# tick-wifi-mini-mk-1_3.net
KiCad netlist of a schematic drawn in EAGLE
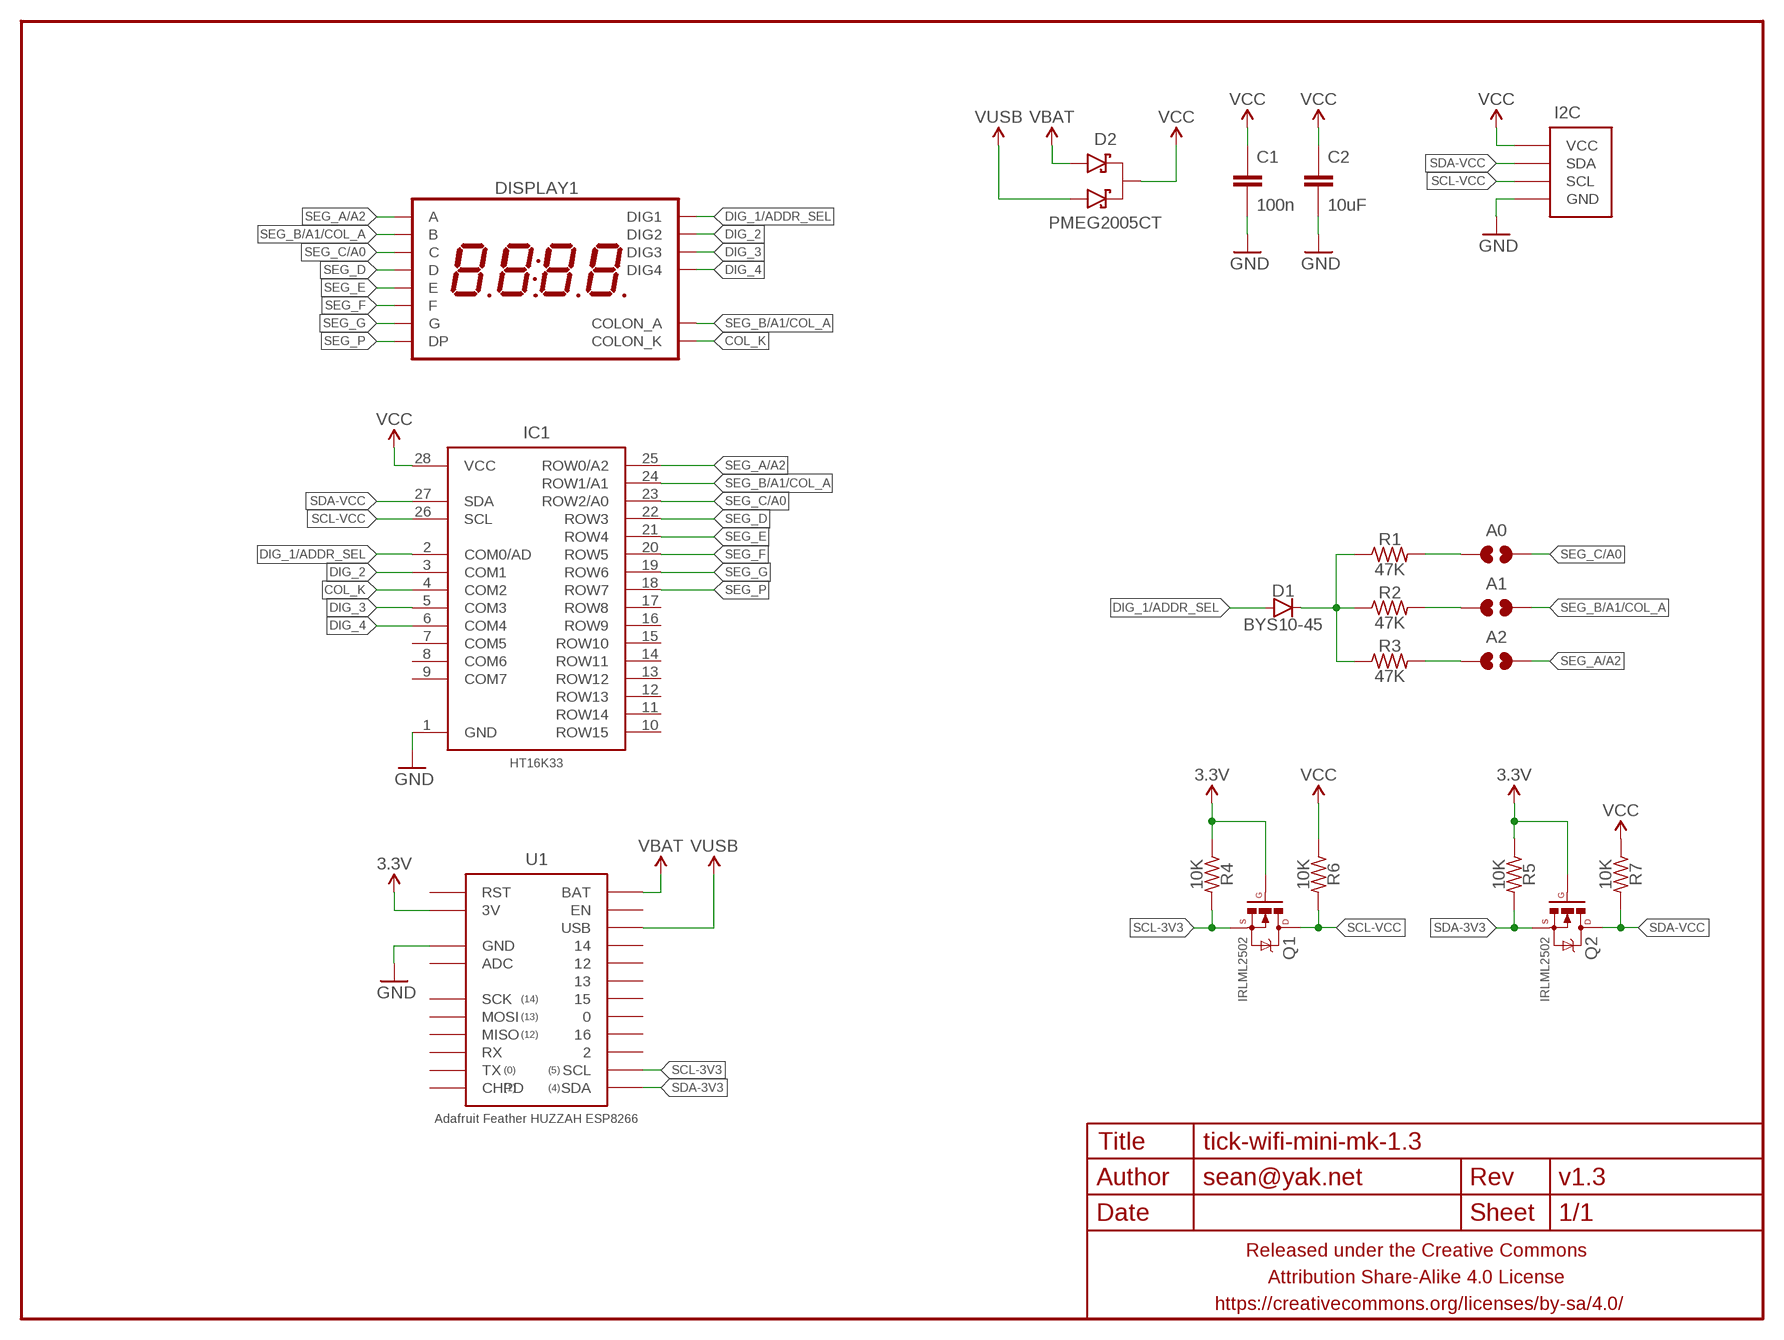
[diagram p0: schematic, sheet 1]

(export (version "E")
  (design (tool "Eeschema 10.0.6"))
  (components
    (comp (ref "A0")
      (value "JUMPER-PAD-2-NOYES_SILK")
      (footprint "eagle-import:PAD-JUMPER-2-NO_YES_SILK")
      (libsource (lib "eagle-import") (part "JUMPER-PAD-2-NOYES_SILK"))
    )
    (comp (ref "A1")
      (value "JUMPER-PAD-2-NOYES_SILK")
      (footprint "eagle-import:PAD-JUMPER-2-NO_YES_SILK")
      (libsource (lib "eagle-import") (part "JUMPER-PAD-2-NOYES_SILK"))
    )
    (comp (ref "A2")
      (value "JUMPER-PAD-2-NOYES_SILK")
      (footprint "eagle-import:PAD-JUMPER-2-NO_YES_SILK")
      (libsource (lib "eagle-import") (part "JUMPER-PAD-2-NOYES_SILK"))
    )
    (comp (ref "C1")
      (value "100n")
      (footprint "eagle-import:C0603-TIGHTER")
      (libsource (lib "eagle-import") (part "CAPACITOR-CERAMICC0603-TIGHTER"))
    )
    (comp (ref "C2")
      (value "10uF")
      (footprint "eagle-import:C0805-TIGHTER")
      (libsource (lib "eagle-import") (part "CAPACITOR-CERAMICC0805-TIGHTER"))
    )
    (comp (ref "D1")
      (value "BYS10-45")
      (footprint "eagle-import:SOD323")
      (libsource (lib "eagle-import") (part "DIODESOD"))
    )
    (comp (ref "D2")
      (value "PMEG2005CT")
      (footprint "eagle-import:SOT23")
      (libsource (lib "eagle-import") (part "DIODE-SCHOTTKY-DUALPMEG2005CT"))
    )
    (comp (ref "DISPLAY1")
      (value "7SEG_4DIGIT_COLON14.2MM-CC")
      (footprint "eagle-import:7SEG_4DIG_0.56IN_14MM_ADAFRUIT")
      (libsource (lib "eagle-import") (part "7SEG_4DIGIT_COLON14.2MM-CC"))
    )
    (comp (ref "FRAME1")
      (value "FRAME-LETTERNO_PACKAGE")
      (footprint "eagle-import:DUMMY")
      (fields (field (name "DESIGNER") "sean@yak.net") (field (name "VERSION") "v1.3"))
      (libsource (lib "eagle-import") (part "FRAME-LETTERNO_PACKAGE"))
    )
    (comp (ref "I2C")
      (value "M04-I2CPTH-2MM-CENTERED")
      (footprint "eagle-import:1X04-2MM-CENTERED-I2C")
      (libsource (lib "eagle-import") (part "M04-I2CPTH-2MM-CENTERED"))
    )
    (comp (ref "IC1")
      (value "HT16K33")
      (footprint "eagle-import:SOIC28W")
      (libsource (lib "eagle-import") (part "HT16K33-28SOIC28W"))
    )
    (comp (ref "Q1")
      (value "IRLML2502")
      (footprint "eagle-import:SOT23")
      (libsource (lib "eagle-import") (part "MOSFET-NCHANNELIRLML2502"))
    )
    (comp (ref "Q2")
      (value "IRLML2502")
      (footprint "eagle-import:SOT23")
      (libsource (lib "eagle-import") (part "MOSFET-NCHANNELIRLML2502"))
    )
    (comp (ref "R1")
      (value "47K")
      (footprint "eagle-import:R0603-TIGHTER")
      (libsource (lib "eagle-import") (part "RESISTORR0603-TIGHTER"))
    )
    (comp (ref "R2")
      (value "47K")
      (footprint "eagle-import:R0603-TIGHTER")
      (libsource (lib "eagle-import") (part "RESISTORR0603-TIGHTER"))
    )
    (comp (ref "R3")
      (value "47K")
      (footprint "eagle-import:R0603-TIGHTER")
      (libsource (lib "eagle-import") (part "RESISTORR0603-TIGHTER"))
    )
    (comp (ref "R4")
      (value "10K")
      (footprint "eagle-import:R0603-TIGHTER")
      (libsource (lib "eagle-import") (part "RESISTORR0603-TIGHTER"))
    )
    (comp (ref "R5")
      (value "10K")
      (footprint "eagle-import:R0603-TIGHTER")
      (libsource (lib "eagle-import") (part "RESISTORR0603-TIGHTER"))
    )
    (comp (ref "R6")
      (value "10K")
      (footprint "eagle-import:R0603-TIGHTER")
      (libsource (lib "eagle-import") (part "RESISTORR0603-TIGHTER"))
    )
    (comp (ref "R7")
      (value "10K")
      (footprint "eagle-import:R0603-TIGHTER")
      (libsource (lib "eagle-import") (part "RESISTORR0603-TIGHTER"))
    )
    (comp (ref "U1")
      (value "Adafruit Feather HUZZAH ESP8266")
      (footprint "eagle-import:ADAFRUIT_FEATHER_HUZZAH_NOSILK")
      (libsource (lib "eagle-import") (part "ADAFRUIT_FEATHER_HUZZAH_ESP8266NOSILK"))
    )
  )
  (nets
    (net (code "1") (name "3.3V") (class "Default")
      (node (ref "Q1") (pin "1") (pinfunction "G_1") (pintype "passive"))
      (node (ref "Q2") (pin "1") (pinfunction "G_1") (pintype "passive"))
      (node (ref "R4") (pin "1") (pinfunction "1_1") (pintype "passive"))
      (node (ref "R5") (pin "1") (pinfunction "1_1") (pintype "passive"))
      (node (ref "U1") (pin "3V") (pinfunction "3V_3V") (pintype "bidirectional"))
    )
    (net (code "2") (name "COL_K") (class "Default")
      (node (ref "DISPLAY1") (pin "P$7") (pinfunction "COLON_K_P$7") (pintype "passive"))
      (node (ref "IC1") (pin "4") (pinfunction "COM2_4") (pintype "bidirectional"))
    )
    (net (code "3") (name "DIG_1{slash}ADDR_SEL") (class "Default")
      (node (ref "D1") (pin "A") (pinfunction "A_A") (pintype "passive"))
      (node (ref "DISPLAY1") (pin "P$14") (pinfunction "DIG1_P$14") (pintype "passive"))
      (node (ref "IC1") (pin "2") (pinfunction "COM0/AD_2") (pintype "bidirectional"))
    )
    (net (code "4") (name "DIG_2") (class "Default")
      (node (ref "DISPLAY1") (pin "P$11") (pinfunction "DIG2_P$11") (pintype "passive"))
      (node (ref "IC1") (pin "3") (pinfunction "COM1_3") (pintype "bidirectional"))
    )
    (net (code "5") (name "DIG_3") (class "Default")
      (node (ref "DISPLAY1") (pin "P$10") (pinfunction "DIG3_P$10") (pintype "passive"))
      (node (ref "IC1") (pin "5") (pinfunction "COM3_5") (pintype "bidirectional"))
    )
    (net (code "6") (name "DIG_4") (class "Default")
      (node (ref "DISPLAY1") (pin "P$6") (pinfunction "DIG4_P$6") (pintype "passive"))
      (node (ref "IC1") (pin "6") (pinfunction "COM4_6") (pintype "bidirectional"))
    )
    (net (code "7") (name "GND") (class "Default")
      (node (ref "C1") (pin "2") (pinfunction "2_2") (pintype "passive"))
      (node (ref "C2") (pin "2") (pinfunction "2_2") (pintype "passive"))
      (node (ref "I2C") (pin "1") (pinfunction "GND_1") (pintype "bidirectional"))
      (node (ref "IC1") (pin "1") (pinfunction "GND_1") (pintype "bidirectional"))
      (node (ref "U1") (pin "GND@0") (pinfunction "GND_GND@0") (pintype "bidirectional"))
    )
    (net (code "8") (name "Net-(A0-Pad1)") (class "Default")
      (node (ref "A0") (pin "1") (pinfunction "1_1") (pintype "passive"))
      (node (ref "R1") (pin "2") (pinfunction "2_2") (pintype "passive"))
    )
    (net (code "9") (name "Net-(A1-Pad1)") (class "Default")
      (node (ref "A1") (pin "1") (pinfunction "1_1") (pintype "passive"))
      (node (ref "R2") (pin "2") (pinfunction "2_2") (pintype "passive"))
    )
    (net (code "10") (name "Net-(A2-Pad1)") (class "Default")
      (node (ref "A2") (pin "1") (pinfunction "1_1") (pintype "passive"))
      (node (ref "R3") (pin "2") (pinfunction "2_2") (pintype "passive"))
    )
    (net (code "11") (name "Net-(D1-PadC)") (class "Default")
      (node (ref "D1") (pin "C") (pinfunction "C_C") (pintype "passive"))
      (node (ref "R1") (pin "1") (pinfunction "1_1") (pintype "passive"))
      (node (ref "R2") (pin "1") (pinfunction "1_1") (pintype "passive"))
      (node (ref "R3") (pin "1") (pinfunction "1_1") (pintype "passive"))
    )
    (net (code "12") (name "SCL-3V3") (class "Default")
      (node (ref "Q1") (pin "2") (pinfunction "S_2") (pintype "passive"))
      (node (ref "R4") (pin "2") (pinfunction "2_2") (pintype "passive"))
      (node (ref "U1") (pin "SCL") (pinfunction "SCL_SCL") (pintype "bidirectional"))
    )
    (net (code "13") (name "SCL-VCC") (class "Default")
      (node (ref "I2C") (pin "4") (pinfunction "SCL_4") (pintype "bidirectional"))
      (node (ref "IC1") (pin "26") (pinfunction "SCL_26") (pintype "bidirectional"))
      (node (ref "Q1") (pin "3") (pinfunction "D_3") (pintype "passive"))
      (node (ref "R6") (pin "2") (pinfunction "2_2") (pintype "passive"))
    )
    (net (code "14") (name "SDA-3V3") (class "Default")
      (node (ref "Q2") (pin "2") (pinfunction "S_2") (pintype "passive"))
      (node (ref "R5") (pin "2") (pinfunction "2_2") (pintype "passive"))
      (node (ref "U1") (pin "SDA") (pinfunction "SDA_SDA") (pintype "bidirectional"))
    )
    (net (code "15") (name "SDA-VCC") (class "Default")
      (node (ref "I2C") (pin "3") (pinfunction "SDA_3") (pintype "bidirectional"))
      (node (ref "IC1") (pin "27") (pinfunction "SDA_27") (pintype "bidirectional"))
      (node (ref "Q2") (pin "3") (pinfunction "D_3") (pintype "passive"))
      (node (ref "R7") (pin "2") (pinfunction "2_2") (pintype "passive"))
    )
    (net (code "16") (name "SEG_A{slash}A2") (class "Default")
      (node (ref "A2") (pin "2") (pinfunction "2_2") (pintype "passive"))
      (node (ref "DISPLAY1") (pin "P$13") (pinfunction "A_P$13") (pintype "passive"))
      (node (ref "IC1") (pin "25") (pinfunction "ROW0/A2_25") (pintype "bidirectional"))
    )
    (net (code "17") (name "SEG_B{slash}A1{slash}COL_A") (class "Default")
      (node (ref "A1") (pin "2") (pinfunction "2_2") (pintype "passive"))
      (node (ref "DISPLAY1") (pin "P$8") (pinfunction "COLON_A_P$8") (pintype "passive"))
      (node (ref "DISPLAY1") (pin "P$9") (pinfunction "B_P$9") (pintype "passive"))
      (node (ref "IC1") (pin "24") (pinfunction "ROW1/A1_24") (pintype "bidirectional"))
    )
    (net (code "18") (name "SEG_C{slash}A0") (class "Default")
      (node (ref "A0") (pin "2") (pinfunction "2_2") (pintype "passive"))
      (node (ref "DISPLAY1") (pin "P$4") (pinfunction "C_P$4") (pintype "passive"))
      (node (ref "IC1") (pin "23") (pinfunction "ROW2/A0_23") (pintype "bidirectional"))
    )
    (net (code "19") (name "SEG_D") (class "Default")
      (node (ref "DISPLAY1") (pin "P$2") (pinfunction "D_P$2") (pintype "passive"))
      (node (ref "IC1") (pin "22") (pinfunction "ROW3_22") (pintype "bidirectional"))
    )
    (net (code "20") (name "SEG_E") (class "Default")
      (node (ref "DISPLAY1") (pin "P$1") (pinfunction "E_P$1") (pintype "passive"))
      (node (ref "IC1") (pin "21") (pinfunction "ROW4_21") (pintype "bidirectional"))
    )
    (net (code "21") (name "SEG_F") (class "Default")
      (node (ref "DISPLAY1") (pin "P$12") (pinfunction "F_P$12") (pintype "passive"))
      (node (ref "IC1") (pin "20") (pinfunction "ROW5_20") (pintype "bidirectional"))
    )
    (net (code "22") (name "SEG_G") (class "Default")
      (node (ref "DISPLAY1") (pin "P$5") (pinfunction "G_P$5") (pintype "passive"))
      (node (ref "IC1") (pin "19") (pinfunction "ROW6_19") (pintype "bidirectional"))
    )
    (net (code "23") (name "SEG_P") (class "Default")
      (node (ref "DISPLAY1") (pin "P$3") (pinfunction "DP_P$3") (pintype "passive"))
      (node (ref "IC1") (pin "18") (pinfunction "ROW7_18") (pintype "bidirectional"))
    )
    (net (code "24") (name "VBAT") (class "Default")
      (node (ref "D2") (pin "1") (pinfunction "A1_1") (pintype "passive"))
      (node (ref "U1") (pin "BAT") (pinfunction "BAT_BAT") (pintype "bidirectional"))
    )
    (net (code "25") (name "VCC") (class "Default")
      (node (ref "C1") (pin "1") (pinfunction "1_1") (pintype "passive"))
      (node (ref "C2") (pin "1") (pinfunction "1_1") (pintype "passive"))
      (node (ref "D2") (pin "3") (pinfunction "K_3") (pintype "passive"))
      (node (ref "I2C") (pin "2") (pinfunction "VCC_2") (pintype "bidirectional"))
      (node (ref "IC1") (pin "28") (pinfunction "VCC_28") (pintype "bidirectional"))
      (node (ref "R6") (pin "1") (pinfunction "1_1") (pintype "passive"))
      (node (ref "R7") (pin "1") (pinfunction "1_1") (pintype "passive"))
    )
    (net (code "26") (name "VUSB") (class "Default")
      (node (ref "D2") (pin "2") (pinfunction "A2_2") (pintype "passive"))
      (node (ref "U1") (pin "USB") (pinfunction "USB_USB") (pintype "bidirectional"))
    )
    (net (code "27") (name "unconnected-(IC1-COM5-Pad7)") (class "Default")
      (node (ref "IC1") (pin "7") (pinfunction "COM5_7") (pintype "bidirectional"))
    )
    (net (code "28") (name "unconnected-(IC1-COM6-Pad8)") (class "Default")
      (node (ref "IC1") (pin "8") (pinfunction "COM6_8") (pintype "bidirectional"))
    )
    (net (code "29") (name "unconnected-(IC1-COM7-Pad9)") (class "Default")
      (node (ref "IC1") (pin "9") (pinfunction "COM7_9") (pintype "bidirectional"))
    )
    (net (code "30") (name "unconnected-(IC1-ROW8-Pad17)") (class "Default")
      (node (ref "IC1") (pin "17") (pinfunction "ROW8_17") (pintype "bidirectional"))
    )
    (net (code "31") (name "unconnected-(IC1-ROW9-Pad16)") (class "Default")
      (node (ref "IC1") (pin "16") (pinfunction "ROW9_16") (pintype "bidirectional"))
    )
    (net (code "32") (name "unconnected-(IC1-ROW10-Pad15)") (class "Default")
      (node (ref "IC1") (pin "15") (pinfunction "ROW10_15") (pintype "bidirectional"))
    )
    (net (code "33") (name "unconnected-(IC1-ROW11-Pad14)") (class "Default")
      (node (ref "IC1") (pin "14") (pinfunction "ROW11_14") (pintype "bidirectional"))
    )
    (net (code "34") (name "unconnected-(IC1-ROW12-Pad13)") (class "Default")
      (node (ref "IC1") (pin "13") (pinfunction "ROW12_13") (pintype "bidirectional"))
    )
    (net (code "35") (name "unconnected-(IC1-ROW13-Pad12)") (class "Default")
      (node (ref "IC1") (pin "12") (pinfunction "ROW13_12") (pintype "bidirectional"))
    )
    (net (code "36") (name "unconnected-(IC1-ROW14-Pad11)") (class "Default")
      (node (ref "IC1") (pin "11") (pinfunction "ROW14_11") (pintype "bidirectional"))
    )
    (net (code "37") (name "unconnected-(IC1-ROW15-Pad10)") (class "Default")
      (node (ref "IC1") (pin "10") (pinfunction "ROW15_10") (pintype "bidirectional"))
    )
    (net (code "38") (name "unconnected-(U1-Pad0)") (class "Default")
      (node (ref "U1") (pin "0") (pinfunction "0_0") (pintype "bidirectional"))
    )
    (net (code "39") (name "unconnected-(U1-Pad2)") (class "Default")
      (node (ref "U1") (pin "2") (pinfunction "2_2") (pintype "bidirectional"))
    )
    (net (code "40") (name "unconnected-(U1-Pad12)") (class "Default")
      (node (ref "U1") (pin "12") (pinfunction "12_12") (pintype "bidirectional"))
    )
    (net (code "41") (name "unconnected-(U1-Pad13)") (class "Default")
      (node (ref "U1") (pin "13") (pinfunction "13_13") (pintype "bidirectional"))
    )
    (net (code "42") (name "unconnected-(U1-Pad14)") (class "Default")
      (node (ref "U1") (pin "14") (pinfunction "14_14") (pintype "bidirectional"))
    )
    (net (code "43") (name "unconnected-(U1-Pad15)") (class "Default")
      (node (ref "U1") (pin "15") (pinfunction "15_15") (pintype "bidirectional"))
    )
    (net (code "44") (name "unconnected-(U1-Pad16)") (class "Default")
      (node (ref "U1") (pin "16") (pinfunction "16_16") (pintype "bidirectional"))
    )
    (net (code "45") (name "unconnected-(U1-PadADC)") (class "Default")
      (node (ref "U1") (pin "ADC") (pinfunction "ADC_ADC") (pintype "bidirectional"))
    )
    (net (code "46") (name "unconnected-(U1-PadCHPD)") (class "Default")
      (node (ref "U1") (pin "CHPD") (pinfunction "CHPD_CHPD") (pintype "bidirectional"))
    )
    (net (code "47") (name "unconnected-(U1-PadEN)") (class "Default")
      (node (ref "U1") (pin "EN") (pinfunction "EN_EN") (pintype "bidirectional"))
    )
    (net (code "48") (name "unconnected-(U1-PadMISO)") (class "Default")
      (node (ref "U1") (pin "MISO") (pinfunction "MISO_MISO") (pintype "bidirectional"))
    )
    (net (code "49") (name "unconnected-(U1-PadMOSI)") (class "Default")
      (node (ref "U1") (pin "MOSI") (pinfunction "MOSI_MOSI") (pintype "bidirectional"))
    )
    (net (code "50") (name "unconnected-(U1-PadRST)") (class "Default")
      (node (ref "U1") (pin "RST") (pinfunction "RST_RST") (pintype "bidirectional"))
    )
    (net (code "51") (name "unconnected-(U1-PadRX)") (class "Default")
      (node (ref "U1") (pin "RX") (pinfunction "RX_RX") (pintype "bidirectional"))
    )
    (net (code "52") (name "unconnected-(U1-PadSCK)") (class "Default")
      (node (ref "U1") (pin "SCK") (pinfunction "SCK_SCK") (pintype "bidirectional"))
    )
    (net (code "53") (name "unconnected-(U1-PadTX)") (class "Default")
      (node (ref "U1") (pin "TX") (pinfunction "TX_TX") (pintype "bidirectional"))
    )
  )
)
